# level_shift.net
KiCad netlist of a schematic drawn in Altium Designer
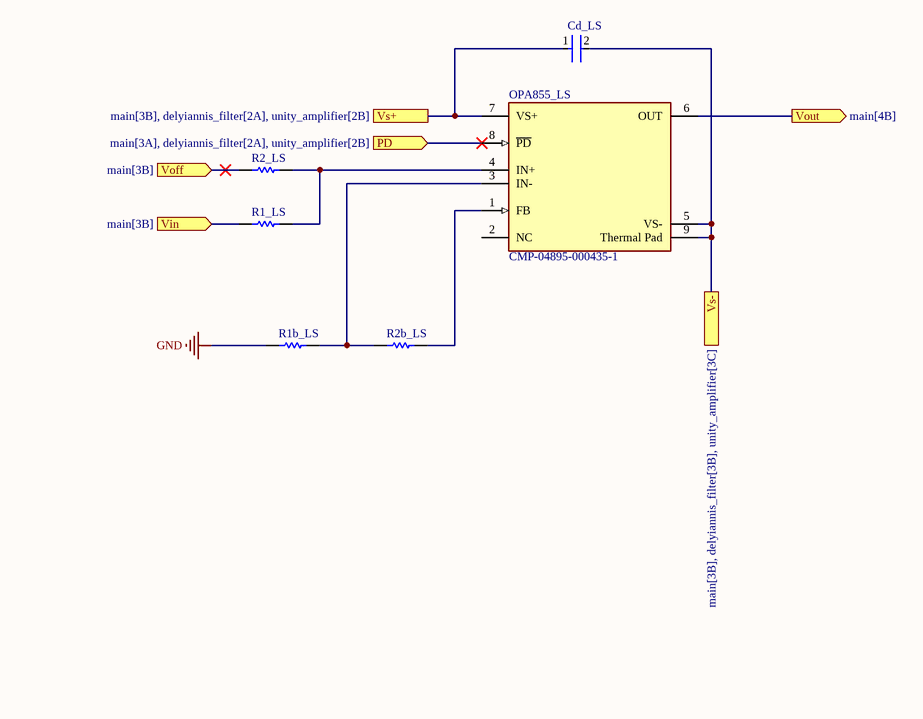
[diagram p0: level_shift.SchDoc]

(export (version "E")
  (design (tool "Eeschema 10.0.6"))
  (components
    (comp (ref "Cd_LS")
      (value "C0402C104K4RACTU")
      (footprint "FP-C0402-BB-MFG")
      (description "CAP CER 0.1UF 16V X7R 0402")
      (fields
        (field (name "TOLERANCE") "0.1")
        (field (name "OCTOPART") "https://octopart.com/c0402c104k4ractu-kemet-94158")
      )
      (libsource (lib "Altium Content Vault") (part "b4654b650e69147ec39a6b967a45e02"))
    )
    (comp (ref "OPA855_LS")
      (value "CMP-04895-000435-1")
      (footprint "FP-DSG0008A-MFG")
      (description "IC OPAMP GP 1 CIRCUIT 8WSON")
      (libsource (lib "kevin kim") (part "CMP-04895-000435-1"))
    )
    (comp (ref "R1b_LS")
      (value "RC0402FR-07100RL")
      (footprint "RESC1005X40X25ML05T10")
      (fields (field (name "MANUFACTURER") "Yageo / Phycomp"))
      (libsource (lib "Altium Content Vault") (part "RES"))
    )
    (comp (ref "R1_LS")
      (value "RC0402FR-07100RL")
      (footprint "RESC1005X40X25ML05T10")
      (fields (field (name "MANUFACTURER") "Yageo / Phycomp"))
      (libsource (lib "Altium Content Vault") (part "RES"))
    )
    (comp (ref "R2b_LS")
      (value "RC0402FR-07100RL")
      (footprint "RESC1005X40X25ML05T10")
      (fields (field (name "MANUFACTURER") "Yageo / Phycomp"))
      (libsource (lib "Altium Content Vault") (part "RES"))
    )
    (comp (ref "R2_LS")
      (value "RC0402FR-07100RL")
      (footprint "RESC1005X40X25ML05T10")
      (fields (field (name "MANUFACTURER") "Yageo / Phycomp"))
      (libsource (lib "Altium Content Vault") (part "RES"))
    )
  )
  (nets
    (net (code "1") (name "/PD") (class "Default")
      (node (ref "OPA855_LS") (pin "8") (pinfunction "~{PD}_8") (pintype "input+no_connect"))
    )
    (net (code "2") (name "/Vin") (class "Default")
      (node (ref "R1_LS") (pin "1") (pinfunction "1_1") (pintype "passive"))
    )
    (net (code "3") (name "/Voff") (class "Default")
      (node (ref "R2_LS") (pin "1") (pinfunction "1_1") (pintype "passive"))
    )
    (net (code "4") (name "/Vout") (class "Default")
      (node (ref "OPA855_LS") (pin "6") (pinfunction "OUT_6") (pintype "passive"))
    )
    (net (code "5") (name "/Vs+") (class "Default")
      (node (ref "Cd_LS") (pin "1") (pinfunction "1_1") (pintype "passive"))
      (node (ref "OPA855_LS") (pin "7") (pinfunction "VS+_7") (pintype "power_in"))
    )
    (net (code "6") (name "/Vs-") (class "Default")
      (node (ref "Cd_LS") (pin "2") (pinfunction "2_2") (pintype "passive"))
      (node (ref "OPA855_LS") (pin "5") (pinfunction "VS-_5") (pintype "power_in"))
      (node (ref "OPA855_LS") (pin "9") (pinfunction "Thermal_Pad_9") (pintype "passive"))
    )
    (net (code "7") (name "GND") (class "Default")
      (node (ref "R1b_LS") (pin "1") (pinfunction "1_1") (pintype "passive"))
    )
    (net (code "8") (name "Net-(OPA855_LS-FB)") (class "Default")
      (node (ref "OPA855_LS") (pin "1") (pinfunction "FB_1") (pintype "input"))
      (node (ref "R2b_LS") (pin "2") (pinfunction "2_2") (pintype "passive"))
    )
    (net (code "9") (name "Net-(OPA855_LS-IN+)") (class "Default")
      (node (ref "OPA855_LS") (pin "4") (pinfunction "IN+_4") (pintype "tri_state"))
      (node (ref "R1_LS") (pin "2") (pinfunction "2_2") (pintype "passive"))
      (node (ref "R2_LS") (pin "2") (pinfunction "2_2") (pintype "passive"))
    )
    (net (code "10") (name "Net-(OPA855_LS-IN-)") (class "Default")
      (node (ref "OPA855_LS") (pin "3") (pinfunction "IN-_3") (pintype "tri_state"))
      (node (ref "R1b_LS") (pin "2") (pinfunction "2_2") (pintype "passive"))
      (node (ref "R2b_LS") (pin "1") (pinfunction "1_1") (pintype "passive"))
    )
    (net (code "11") (name "unconnected-(OPA855_LS-NC-Pad2)") (class "Default")
      (node (ref "OPA855_LS") (pin "2") (pinfunction "NC_2") (pintype "passive"))
    )
  )
)
